# Fulmar_v_1_1_0.net
KiCad netlist of a schematic drawn in EAGLE
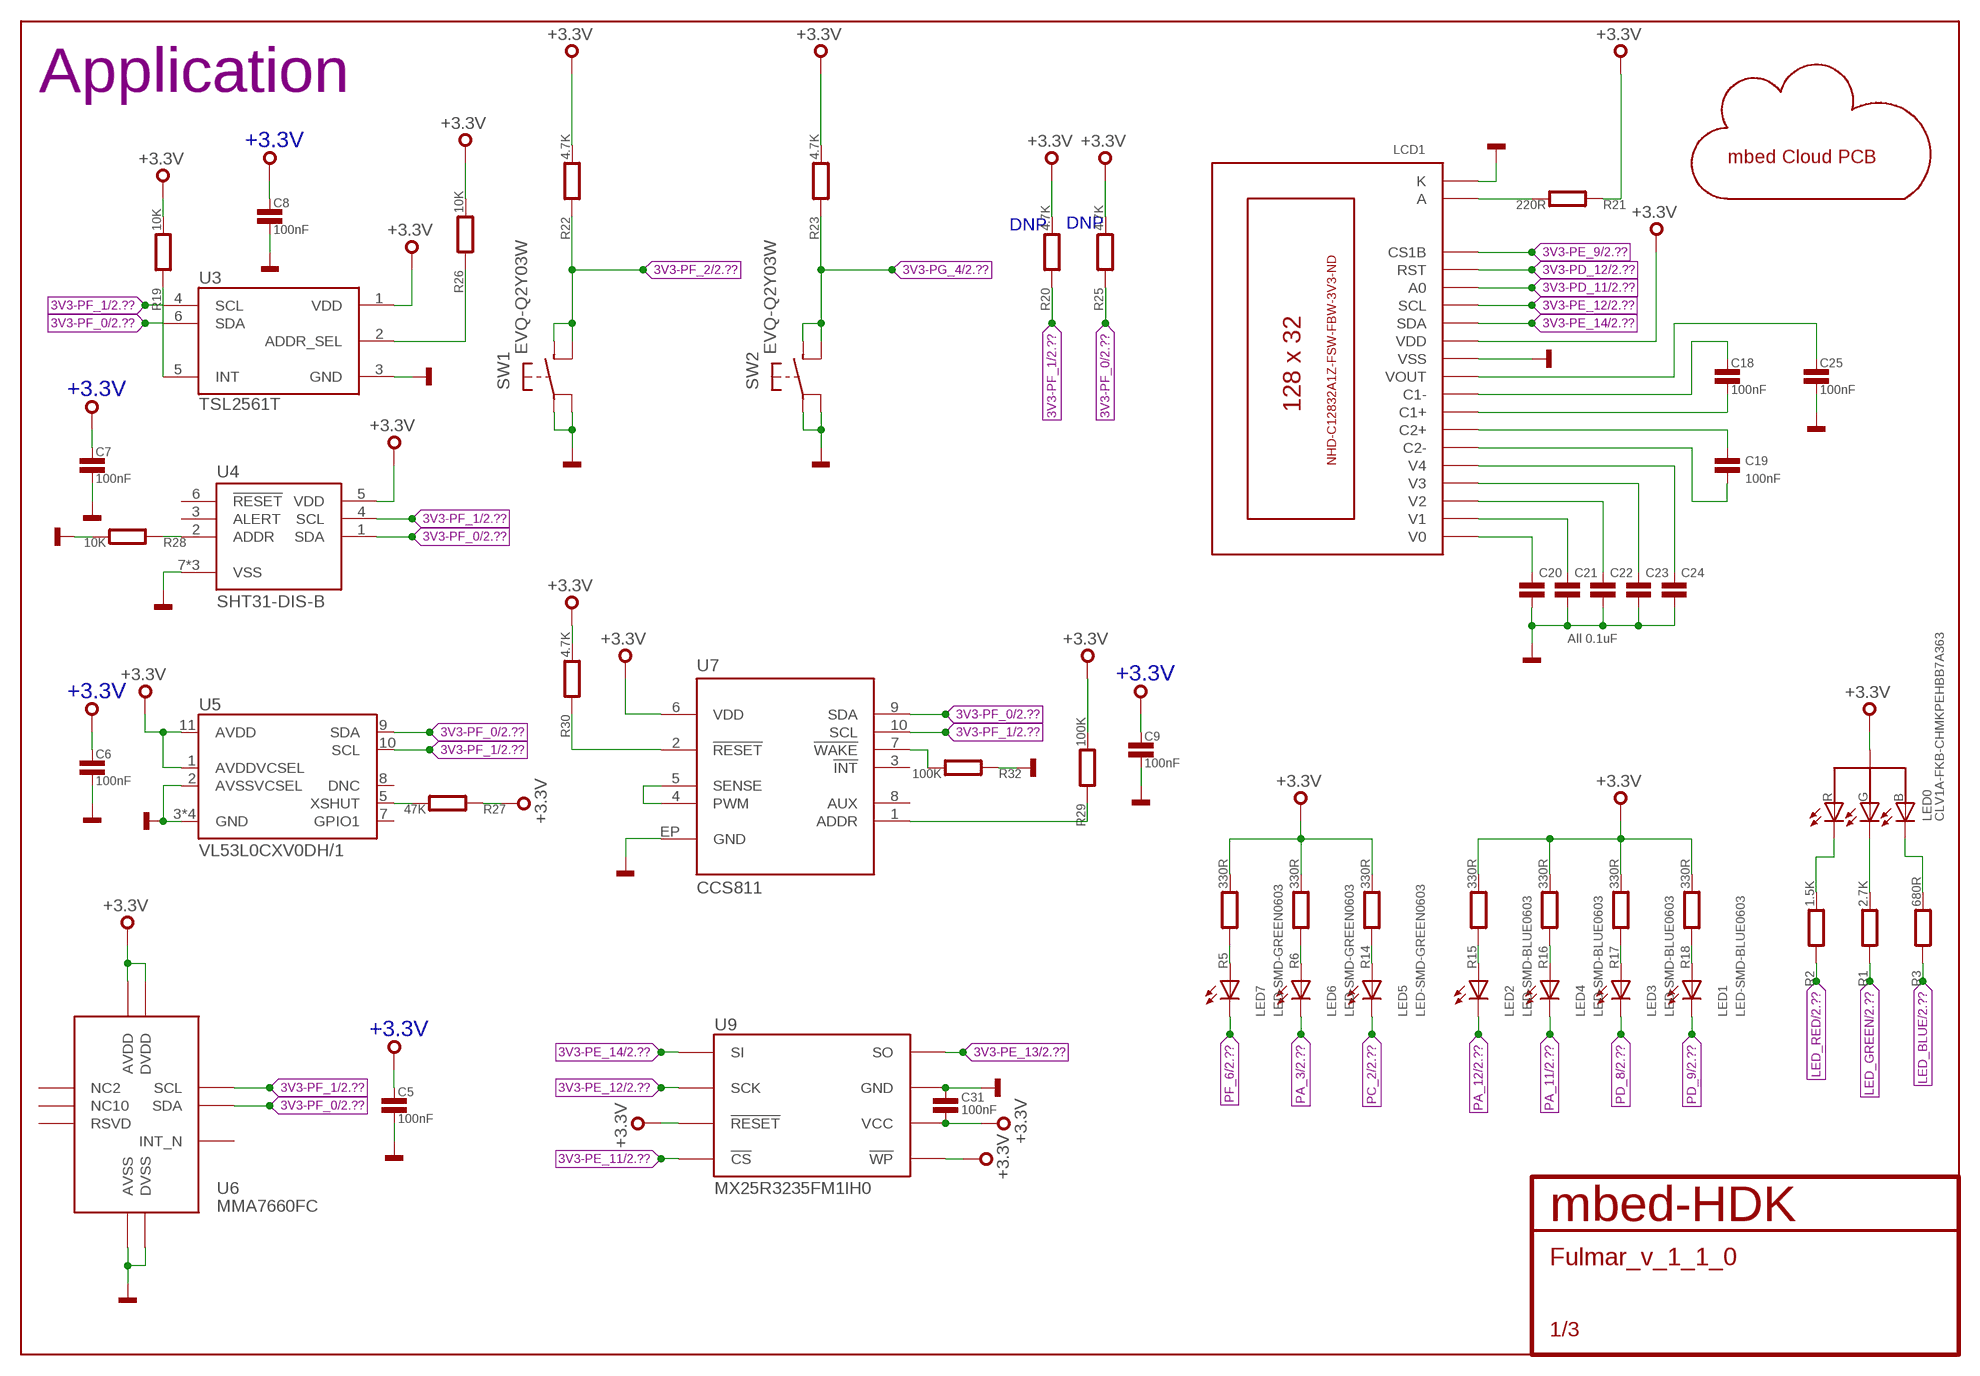
[diagram p0: schematic, sheet 1]
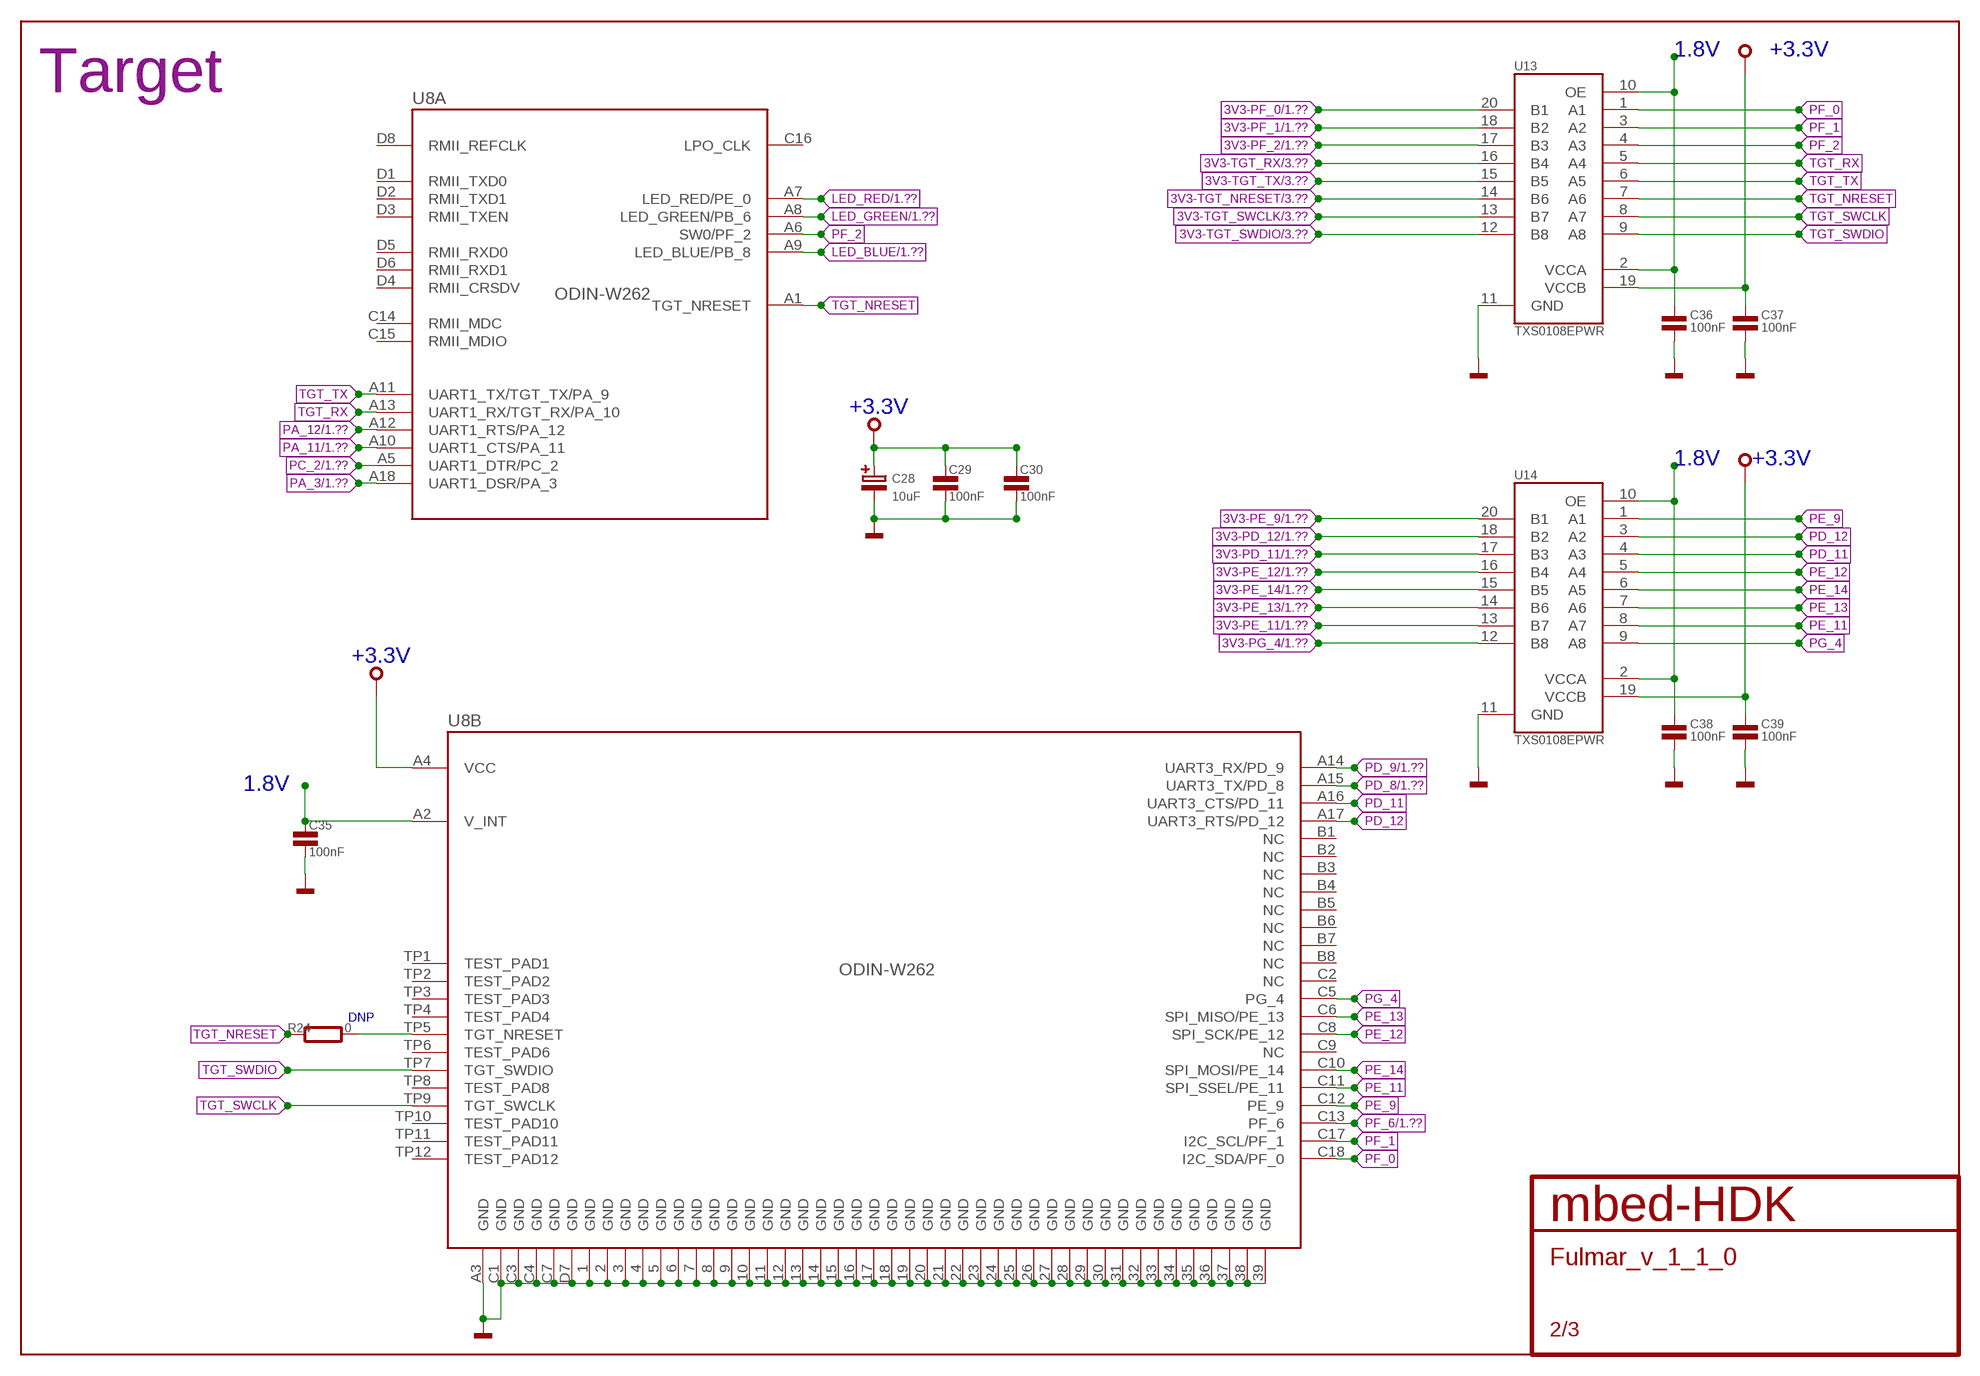
[diagram p1: schematic, sheet 2]
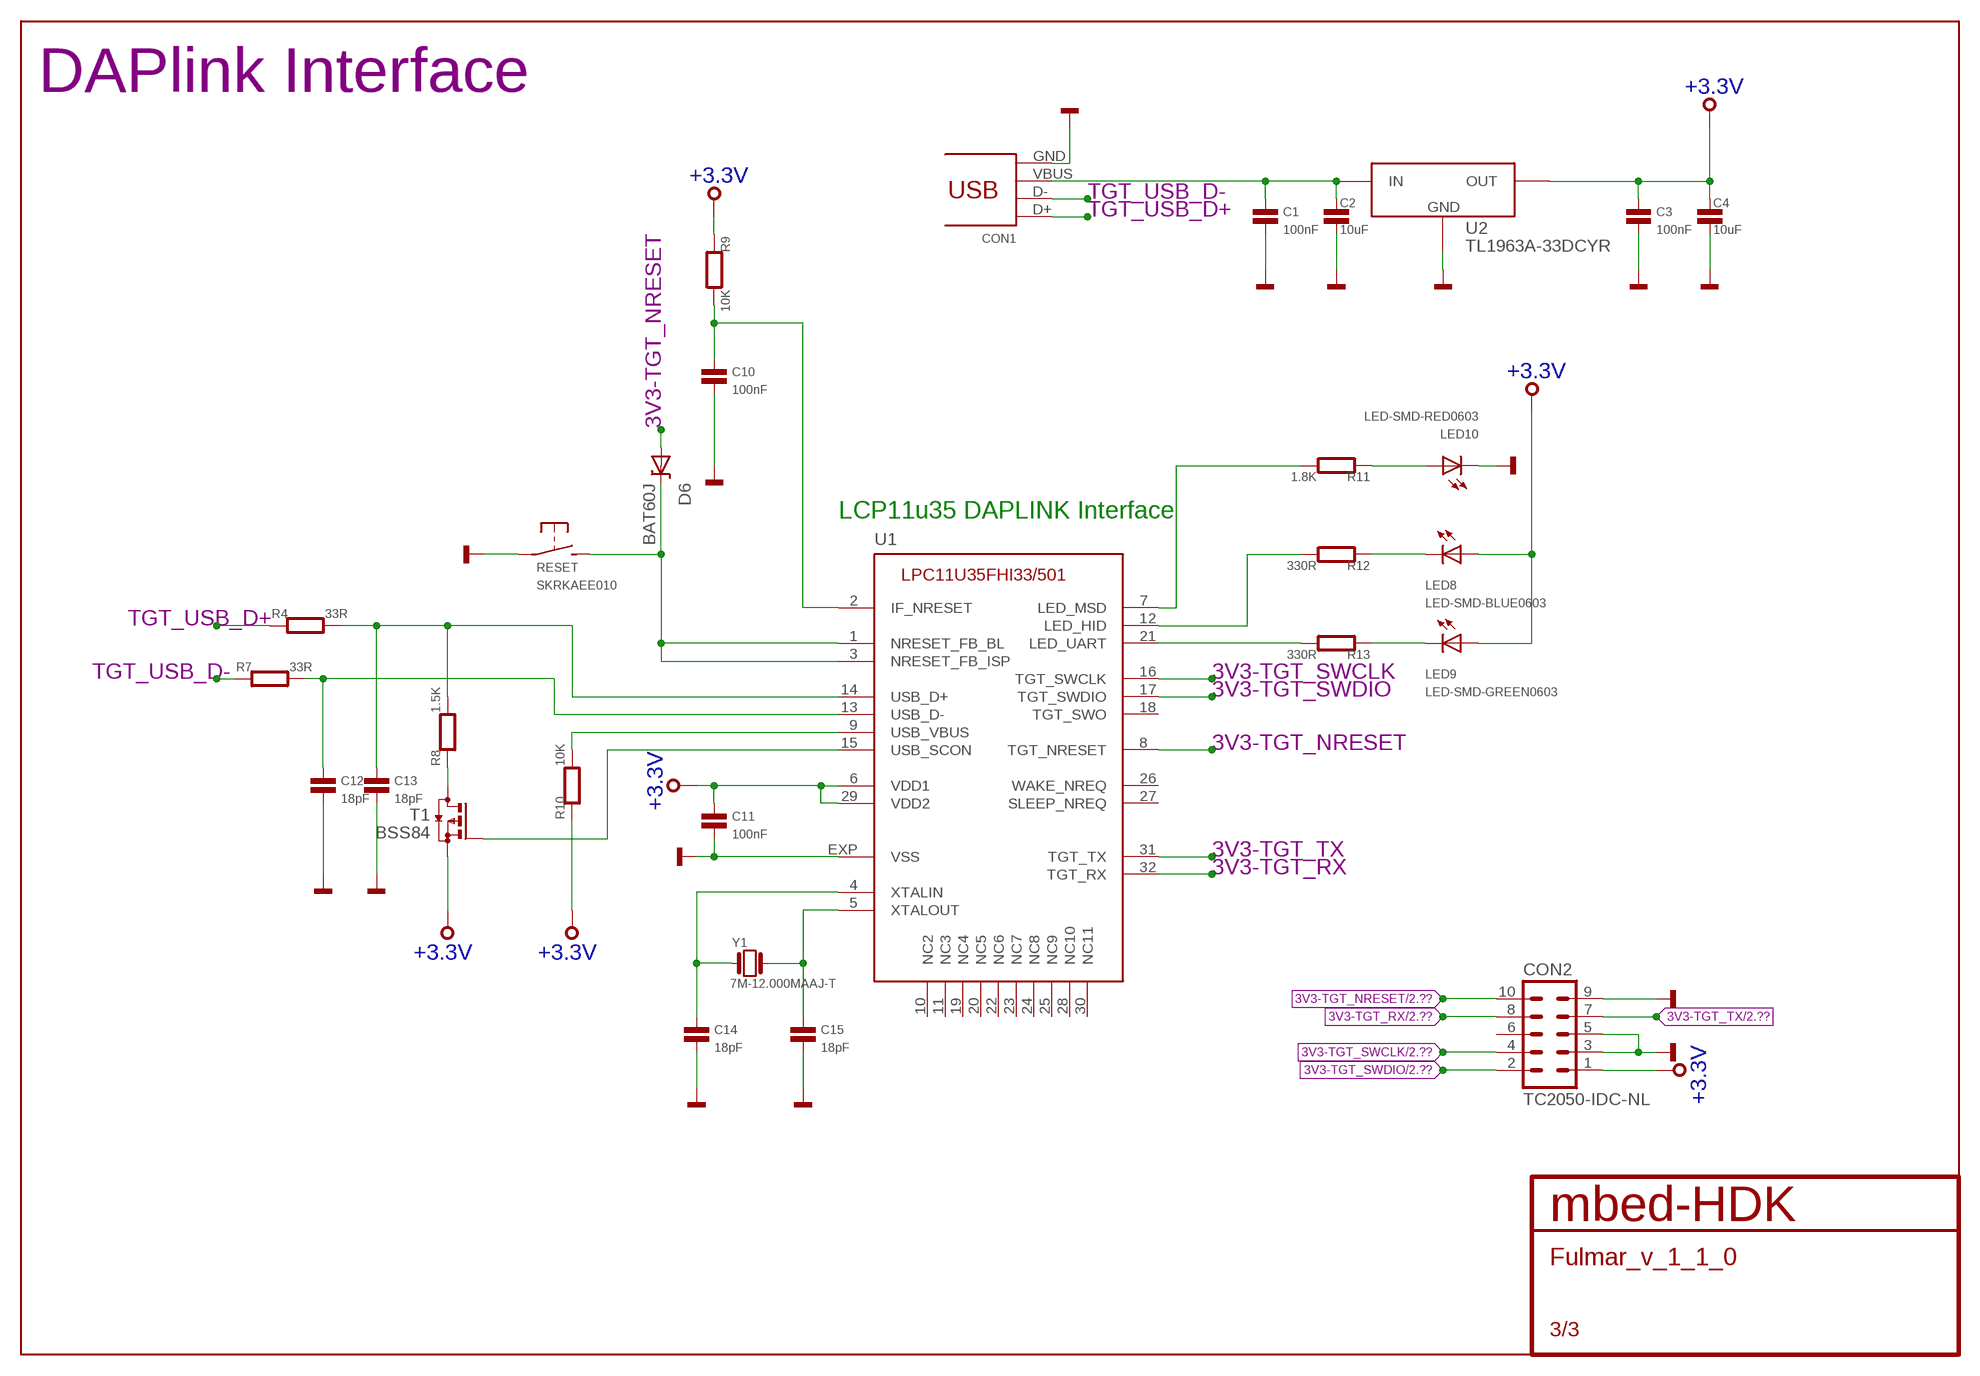
[diagram p2: schematic, sheet 3]

(export (version "E")
  (design (tool "Eeschema 10.0.6"))
  (components
    (comp (ref "C1")
      (value "100nF")
      (footprint "eagle-import:0402")
      (libsource (lib "eagle-import") (part "mbed-HDK-RLCQ_CAPACITOR0402"))
    )
    (comp (ref "C2")
      (value "10uF")
      (footprint "eagle-import:0603")
      (libsource (lib "eagle-import") (part "CAPACITOR0603"))
    )
    (comp (ref "C3")
      (value "100nF")
      (footprint "eagle-import:0402")
      (libsource (lib "eagle-import") (part "mbed-HDK-RLCQ_CAPACITOR0402"))
    )
    (comp (ref "C4")
      (value "10uF")
      (footprint "eagle-import:0603")
      (libsource (lib "eagle-import") (part "CAPACITOR0603"))
    )
    (comp (ref "C10")
      (value "100nF")
      (footprint "eagle-import:0402")
      (libsource (lib "eagle-import") (part "mbed-HDK-RLCQ_CAPACITOR0402"))
    )
    (comp (ref "C11")
      (value "100nF")
      (footprint "eagle-import:0402")
      (libsource (lib "eagle-import") (part "mbed-HDK-RLCQ_CAPACITOR0402"))
    )
    (comp (ref "C12")
      (value "18pF")
      (footprint "eagle-import:0402")
      (libsource (lib "eagle-import") (part "mbed-HDK-RLCQ_CAPACITOR0402"))
    )
    (comp (ref "C13")
      (value "18pF")
      (footprint "eagle-import:0402")
      (libsource (lib "eagle-import") (part "mbed-HDK-RLCQ_CAPACITOR0402"))
    )
    (comp (ref "C14")
      (value "18pF")
      (footprint "eagle-import:0402")
      (libsource (lib "eagle-import") (part "mbed-HDK-RLCQ_CAPACITOR0402"))
    )
    (comp (ref "C15")
      (value "18pF")
      (footprint "eagle-import:0402")
      (libsource (lib "eagle-import") (part "mbed-HDK-RLCQ_CAPACITOR0402"))
    )
    (comp (ref "CON1")
      (value "47346-0001")
      (footprint "eagle-import:USB-MICRO-B-H")
      (fields (field (name "MF") "MOLEX"))
      (libsource (lib "eagle-import") (part "47346-0001"))
    )
    (comp (ref "CON2")
      (value "TC2050-IDC-NL")
      (footprint "eagle-import:TC2050-IDC-NL")
      (libsource (lib "eagle-import") (part "TC2050-IDC-NL"))
    )
    (comp (ref "D6")
      (value "BAT60J")
      (footprint "eagle-import:SOD323")
      (fields (field (name "MF") "STMicroelectronics"))
      (libsource (lib "eagle-import") (part "BAT60J"))
    )
    (comp (ref "LED8")
      (value "LED-SMD-BLUE0603")
      (footprint "eagle-import:CHIPLED_0603")
      (fields (field (name "MF") "Wurth Electronics Inc"))
      (libsource (lib "eagle-import") (part "LED-SMD-BLUE0603"))
    )
    (comp (ref "LED9")
      (value "LED-SMD-GREEN0603")
      (footprint "eagle-import:CHIPLED_0603")
      (fields (field (name "MF") "Wurth Electronics Inc"))
      (libsource (lib "eagle-import") (part "LED-SMD-GREEN0603"))
    )
    (comp (ref "LED10")
      (value "LED-SMD-RED0603")
      (footprint "eagle-import:CHIPLED_0603")
      (fields (field (name "MF") "Wurth Electronics Inc"))
      (libsource (lib "eagle-import") (part "LED-SMD-RED0603"))
    )
    (comp (ref "R4")
      (value "33R")
      (footprint "eagle-import:0402")
      (libsource (lib "eagle-import") (part "mbed-HDK-RLCQ_RESISTOR0402"))
    )
    (comp (ref "R7")
      (value "33R")
      (footprint "eagle-import:0402")
      (libsource (lib "eagle-import") (part "mbed-HDK-RLCQ_RESISTOR0402"))
    )
    (comp (ref "R8")
      (value "1.5K")
      (footprint "eagle-import:0402")
      (libsource (lib "eagle-import") (part "mbed-HDK-RLCQ_RESISTOR0402"))
    )
    (comp (ref "R9")
      (value "10K")
      (footprint "eagle-import:0402")
      (libsource (lib "eagle-import") (part "mbed-HDK-RLCQ_RESISTOR0402"))
    )
    (comp (ref "R10")
      (value "10K")
      (footprint "eagle-import:0402")
      (libsource (lib "eagle-import") (part "mbed-HDK-RLCQ_RESISTOR0402"))
    )
    (comp (ref "R11")
      (value "1.8K")
      (footprint "eagle-import:0402")
      (libsource (lib "eagle-import") (part "mbed-HDK-RLCQ_RESISTOR0402"))
    )
    (comp (ref "R12")
      (value "330R")
      (footprint "eagle-import:0402")
      (libsource (lib "eagle-import") (part "mbed-HDK-RLCQ_RESISTOR0402"))
    )
    (comp (ref "R13")
      (value "330R")
      (footprint "eagle-import:0402")
      (libsource (lib "eagle-import") (part "mbed-HDK-RLCQ_RESISTOR0402"))
    )
    (comp (ref "RESET")
      (value "SKRKAEE010")
      (footprint "eagle-import:SKRKAEE010")
      (fields (field (name "MF") "ALPS"))
      (libsource (lib "eagle-import") (part "SKRKAEE010"))
    )
    (comp (ref "T1")
      (value "BSS84")
      (footprint "eagle-import:SOT23-3")
      (fields (field (name "MF") "Fairchild Semiconductor"))
      (libsource (lib "eagle-import") (part "BSS84"))
    )
    (comp (ref "U1")
      (value "IF_LPC11U35FHI33/501")
      (footprint "eagle-import:HVQFN33")
      (fields (field (name "MF") "NXP"))
      (libsource (lib "eagle-import") (part "IF_LPC11U35FHI33/501"))
    )
    (comp (ref "U2")
      (value "TL1963A-33DCYR")
      (footprint "eagle-import:SOT223")
      (fields (field (name "MF") "Texas Instruments"))
      (libsource (lib "eagle-import") (part "TL1963A-33DCYR"))
    )
    (comp (ref "Y1")
      (value "7M-12.000MAAJ-T")
      (footprint "eagle-import:3.2X.2.5")
      (fields (field (name "MF") "TXC"))
      (libsource (lib "eagle-import") (part "7M-12.000MAAJ-T"))
    )
    (comp (ref "C5")
      (value "100nF")
      (footprint "eagle-import:0603")
      (libsource (lib "eagle-import") (part "CAPACITOR0603"))
    )
    (comp (ref "C6")
      (value "100nF")
      (footprint "eagle-import:0603")
      (libsource (lib "eagle-import") (part "CAPACITOR0603"))
    )
    (comp (ref "C7")
      (value "100nF")
      (footprint "eagle-import:0603")
      (libsource (lib "eagle-import") (part "CAPACITOR0603"))
    )
    (comp (ref "C8")
      (value "100nF")
      (footprint "eagle-import:0603")
      (libsource (lib "eagle-import") (part "CAPACITOR0603"))
    )
    (comp (ref "C9")
      (value "100nF")
      (footprint "eagle-import:0603")
      (libsource (lib "eagle-import") (part "CAPACITOR0603"))
    )
    (comp (ref "C18")
      (value "100nF")
      (footprint "eagle-import:0402")
      (libsource (lib "eagle-import") (part "CAPACITOR0402"))
    )
    (comp (ref "C19")
      (value "100nF")
      (footprint "eagle-import:0402")
      (libsource (lib "eagle-import") (part "CAPACITOR0402"))
    )
    (comp (ref "C20")
      (value "100nF")
      (footprint "eagle-import:0402")
      (libsource (lib "eagle-import") (part "CAPACITOR0402"))
    )
    (comp (ref "C21")
      (value "100nF")
      (footprint "eagle-import:0402")
      (libsource (lib "eagle-import") (part "CAPACITOR0402"))
    )
    (comp (ref "C22")
      (value "100nF")
      (footprint "eagle-import:0402")
      (libsource (lib "eagle-import") (part "CAPACITOR0402"))
    )
    (comp (ref "C23")
      (value "100nF")
      (footprint "eagle-import:0402")
      (libsource (lib "eagle-import") (part "CAPACITOR0402"))
    )
    (comp (ref "C24")
      (value "100nF")
      (footprint "eagle-import:0402")
      (libsource (lib "eagle-import") (part "CAPACITOR0402"))
    )
    (comp (ref "C25")
      (value "100nF")
      (footprint "eagle-import:0402")
      (libsource (lib "eagle-import") (part "CAPACITOR0402"))
    )
    (comp (ref "C31")
      (value "100nF")
      (footprint "eagle-import:0603")
      (libsource (lib "eagle-import") (part "CAPACITOR0603"))
    )
    (comp (ref "LCD1")
      (value "C12832A1Z")
      (footprint "eagle-import:C12832A1Z")
      (libsource (lib "eagle-import") (part "C12832A1Z"))
    )
    (comp (ref "LED0")
      (value "CLV1A-FKB-CHMKPEHBB7A363")
      (footprint "eagle-import:CLV1A-FKB-CHMKPEHBB7A363")
      (fields (field (name "MF") "Cree"))
      (libsource (lib "eagle-import") (part "CLV1A-FKB-CHMKPEHBB7A363"))
    )
    (comp (ref "LED1")
      (value "LED-SMD-BLUE0603")
      (footprint "eagle-import:CHIPLED_0603")
      (fields (field (name "MF") "Wurth Electronics Inc"))
      (libsource (lib "eagle-import") (part "LED-SMD-BLUE0603"))
    )
    (comp (ref "LED2")
      (value "LED-SMD-BLUE0603")
      (footprint "eagle-import:CHIPLED_0603")
      (fields (field (name "MF") "Wurth Electronics Inc"))
      (libsource (lib "eagle-import") (part "LED-SMD-BLUE0603"))
    )
    (comp (ref "LED3")
      (value "LED-SMD-BLUE0603")
      (footprint "eagle-import:CHIPLED_0603")
      (fields (field (name "MF") "Wurth Electronics Inc"))
      (libsource (lib "eagle-import") (part "LED-SMD-BLUE0603"))
    )
    (comp (ref "LED4")
      (value "LED-SMD-BLUE0603")
      (footprint "eagle-import:CHIPLED_0603")
      (fields (field (name "MF") "Wurth Electronics Inc"))
      (libsource (lib "eagle-import") (part "LED-SMD-BLUE0603"))
    )
    (comp (ref "LED5")
      (value "LED-SMD-GREEN0603")
      (footprint "eagle-import:CHIPLED_0603")
      (fields (field (name "MF") "Wurth Electronics Inc"))
      (libsource (lib "eagle-import") (part "LED-SMD-GREEN0603"))
    )
    (comp (ref "LED6")
      (value "LED-SMD-GREEN0603")
      (footprint "eagle-import:CHIPLED_0603")
      (fields (field (name "MF") "Wurth Electronics Inc"))
      (libsource (lib "eagle-import") (part "LED-SMD-GREEN0603"))
    )
    (comp (ref "LED7")
      (value "LED-SMD-GREEN0603")
      (footprint "eagle-import:CHIPLED_0603")
      (fields (field (name "MF") "Wurth Electronics Inc"))
      (libsource (lib "eagle-import") (part "LED-SMD-GREEN0603"))
    )
    (comp (ref "R1")
      (value "2.7K")
      (footprint "eagle-import:0402")
      (libsource (lib "eagle-import") (part "RESISTOR0402"))
    )
    (comp (ref "R2")
      (value "1.5K")
      (footprint "eagle-import:0402")
      (libsource (lib "eagle-import") (part "RESISTOR0402"))
    )
    (comp (ref "R3")
      (value "680R")
      (footprint "eagle-import:0402")
      (libsource (lib "eagle-import") (part "RESISTOR0402"))
    )
    (comp (ref "R5")
      (value "330R")
      (footprint "eagle-import:0402")
      (libsource (lib "eagle-import") (part "RESISTOR0402"))
    )
    (comp (ref "R6")
      (value "330R")
      (footprint "eagle-import:0402")
      (libsource (lib "eagle-import") (part "RESISTOR0402"))
    )
    (comp (ref "R14")
      (value "330R")
      (footprint "eagle-import:0402")
      (libsource (lib "eagle-import") (part "RESISTOR0402"))
    )
    (comp (ref "R15")
      (value "330R")
      (footprint "eagle-import:0402")
      (libsource (lib "eagle-import") (part "RESISTOR0402"))
    )
    (comp (ref "R16")
      (value "330R")
      (footprint "eagle-import:0402")
      (libsource (lib "eagle-import") (part "RESISTOR0402"))
    )
    (comp (ref "R17")
      (value "330R")
      (footprint "eagle-import:0402")
      (libsource (lib "eagle-import") (part "RESISTOR0402"))
    )
    (comp (ref "R18")
      (value "330R")
      (footprint "eagle-import:0402")
      (libsource (lib "eagle-import") (part "RESISTOR0402"))
    )
    (comp (ref "R19")
      (value "10K")
      (footprint "eagle-import:0402")
      (libsource (lib "eagle-import") (part "RESISTOR0402"))
    )
    (comp (ref "R20")
      (value "4.7K")
      (footprint "eagle-import:0402")
      (libsource (lib "eagle-import") (part "RESISTOR0402"))
    )
    (comp (ref "R21")
      (value "220R")
      (footprint "eagle-import:0402")
      (libsource (lib "eagle-import") (part "RESISTOR0402"))
    )
    (comp (ref "R22")
      (value "4.7K")
      (footprint "eagle-import:0402")
      (libsource (lib "eagle-import") (part "RESISTOR0402"))
    )
    (comp (ref "R23")
      (value "4.7K")
      (footprint "eagle-import:0402")
      (libsource (lib "eagle-import") (part "RESISTOR0402"))
    )
    (comp (ref "R25")
      (value "4.7K")
      (footprint "eagle-import:0402")
      (libsource (lib "eagle-import") (part "RESISTOR0402"))
    )
    (comp (ref "R26")
      (value "10K")
      (footprint "eagle-import:0402")
      (libsource (lib "eagle-import") (part "RESISTOR0402"))
    )
    (comp (ref "R27")
      (value "47K")
      (footprint "eagle-import:0402")
      (libsource (lib "eagle-import") (part "RESISTOR0402"))
    )
    (comp (ref "R28")
      (value "10K")
      (footprint "eagle-import:0402")
      (libsource (lib "eagle-import") (part "RESISTOR0402"))
    )
    (comp (ref "R29")
      (value "100K")
      (footprint "eagle-import:0402")
      (libsource (lib "eagle-import") (part "RESISTOR0402"))
    )
    (comp (ref "R30")
      (value "4.7K")
      (footprint "eagle-import:0402")
      (libsource (lib "eagle-import") (part "RESISTOR0402"))
    )
    (comp (ref "R32")
      (value "100K")
      (footprint "eagle-import:0402")
      (libsource (lib "eagle-import") (part "RESISTOR0402"))
    )
    (comp (ref "SW1")
      (value "EVQ-Q2Y03W")
      (footprint "eagle-import:EVQ-Q2Y03W")
      (fields (field (name "MF") "Panasonic"))
      (libsource (lib "eagle-import") (part "EVQ-Q2Y03W"))
    )
    (comp (ref "SW2")
      (value "EVQ-Q2Y03W")
      (footprint "eagle-import:EVQ-Q2Y03W")
      (fields (field (name "MF") "Panasonic"))
      (libsource (lib "eagle-import") (part "EVQ-Q2Y03W"))
    )
    (comp (ref "U$2")
      (value "MBEDCLOUDPCB")
      (footprint "eagle-import:MBEDCLOUDPCB")
      (libsource (lib "eagle-import") (part "MBEDCLOUDPCB"))
    )
    (comp (ref "U3")
      (value "TSL2561T")
      (footprint "eagle-import:6-TMB")
      (fields (field (name "MF") "ams"))
      (libsource (lib "eagle-import") (part "TSL2561T"))
    )
    (comp (ref "U4")
      (value "SHT31-DIS-B")
      (footprint "eagle-import:8-DFN")
      (fields (field (name "MF") "Sensirion"))
      (libsource (lib "eagle-import") (part "SHT31-DIS-B"))
    )
    (comp (ref "U5")
      (value "VL53L0CXV0DH/1")
      (footprint "eagle-import:VL53L0CXV0DH_1")
      (fields (field (name "MF") "ST Microelectronics"))
      (libsource (lib "eagle-import") (part "VL53L0CXV0DH/1"))
    )
    (comp (ref "U6")
      (value "MMA7660FC")
      (footprint "eagle-import:DFN10-3X3MM")
      (fields (field (name "MF") "NXP"))
      (libsource (lib "eagle-import") (part "MMA7660FC"))
    )
    (comp (ref "U7")
      (value "CCS811")
      (footprint "eagle-import:LGA10")
      (fields (field (name "MF") "ams"))
      (libsource (lib "eagle-import") (part "CCS811"))
    )
    (comp (ref "U9")
      (value "MX25R3235FM1IH0")
      (footprint "eagle-import:SO8")
      (fields (field (name "MF") "Macronix"))
      (libsource (lib "eagle-import") (part "MX25R3235FM1IH0"))
    )
    (comp (ref "C28")
      (value "10uF")
      (footprint "eagle-import:SMC_B")
      (fields (field (name "MF") "Kemet"))
      (libsource (lib "eagle-import") (part "CAPACITOR-POLARISEDB"))
    )
    (comp (ref "C29")
      (value "100nF")
      (footprint "eagle-import:0603")
      (libsource (lib "eagle-import") (part "CAPACITOR0603"))
    )
    (comp (ref "C30")
      (value "100nF")
      (footprint "eagle-import:0603")
      (libsource (lib "eagle-import") (part "CAPACITOR0603"))
    )
    (comp (ref "C35")
      (value "100nF")
      (footprint "eagle-import:0603")
      (libsource (lib "eagle-import") (part "CAPACITOR0603"))
    )
    (comp (ref "C36")
      (value "100nF")
      (footprint "eagle-import:0603")
      (libsource (lib "eagle-import") (part "CAPACITOR0603"))
    )
    (comp (ref "C37")
      (value "100nF")
      (footprint "eagle-import:0603")
      (libsource (lib "eagle-import") (part "CAPACITOR0603"))
    )
    (comp (ref "C38")
      (value "100nF")
      (footprint "eagle-import:0603")
      (libsource (lib "eagle-import") (part "CAPACITOR0603"))
    )
    (comp (ref "C39")
      (value "100nF")
      (footprint "eagle-import:0603")
      (libsource (lib "eagle-import") (part "CAPACITOR0603"))
    )
    (comp (ref "R24")
      (value "0")
      (footprint "eagle-import:0402")
      (libsource (lib "eagle-import") (part "RESISTOR0402"))
    )
    (comp (ref "U8")
      (value "ODIN-W262")
      (footprint "eagle-import:ODIN-88")
      (libsource (lib "eagle-import") (part "ODIN-W262"))
    )
    (comp (ref "U13")
      (value "TXS0108EPWR")
      (footprint "eagle-import:TSSOP-20")
      (fields (field (name "MF") "Texas Instruments"))
      (libsource (lib "eagle-import") (part "TXS0108EPWR"))
    )
    (comp (ref "U14")
      (value "TXS0108EPWR")
      (footprint "eagle-import:TSSOP-20")
      (fields (field (name "MF") "Texas Instruments"))
      (libsource (lib "eagle-import") (part "TXS0108EPWR"))
    )
  )
  (nets
    (net (code "1") (name "+3.3V") (class "Default")
      (node (ref "C11") (pin "1") (pinfunction "P$1_1") (pintype "passive"))
      (node (ref "C28") (pin "+") (pinfunction "+_+") (pintype "passive"))
      (node (ref "C29") (pin "1") (pinfunction "P$1_1") (pintype "passive"))
      (node (ref "C3") (pin "1") (pinfunction "P$1_1") (pintype "passive"))
      (node (ref "C30") (pin "1") (pinfunction "P$1_1") (pintype "passive"))
      (node (ref "C31") (pin "2") (pinfunction "P$2_2") (pintype "passive"))
      (node (ref "C37") (pin "1") (pinfunction "P$1_1") (pintype "passive"))
      (node (ref "C39") (pin "1") (pinfunction "P$1_1") (pintype "passive"))
      (node (ref "C4") (pin "1") (pinfunction "P$1_1") (pintype "passive"))
      (node (ref "C5") (pin "1") (pinfunction "P$1_1") (pintype "passive"))
      (node (ref "C6") (pin "1") (pinfunction "P$1_1") (pintype "passive"))
      (node (ref "C7") (pin "1") (pinfunction "P$1_1") (pintype "passive"))
      (node (ref "C8") (pin "1") (pinfunction "P$1_1") (pintype "passive"))
      (node (ref "C9") (pin "1") (pinfunction "P$1_1") (pintype "passive"))
      (node (ref "CON2") (pin "1") (pinfunction "1_1") (pintype "passive"))
      (node (ref "LCD1") (pin "P$12") (pinfunction "VDD_P$12") (pintype "bidirectional"))
      (node (ref "LED0") (pin "2") (pinfunction "2_2") (pintype "passive"))
      (node (ref "LED8") (pin "A") (pinfunction "A_A") (pintype "passive"))
      (node (ref "LED9") (pin "A") (pinfunction "A_A") (pintype "passive"))
      (node (ref "R10") (pin "1") (pinfunction "P$1_1") (pintype "passive"))
      (node (ref "R14") (pin "2") (pinfunction "P$2_2") (pintype "passive"))
      (node (ref "R15") (pin "2") (pinfunction "P$2_2") (pintype "passive"))
      (node (ref "R16") (pin "2") (pinfunction "P$2_2") (pintype "passive"))
      (node (ref "R17") (pin "2") (pinfunction "P$2_2") (pintype "passive"))
      (node (ref "R18") (pin "2") (pinfunction "P$2_2") (pintype "passive"))
      (node (ref "R19") (pin "2") (pinfunction "P$2_2") (pintype "passive"))
      (node (ref "R20") (pin "2") (pinfunction "P$2_2") (pintype "passive"))
      (node (ref "R21") (pin "1") (pinfunction "P$1_1") (pintype "passive"))
      (node (ref "R22") (pin "2") (pinfunction "P$2_2") (pintype "passive"))
      (node (ref "R23") (pin "2") (pinfunction "P$2_2") (pintype "passive"))
      (node (ref "R25") (pin "2") (pinfunction "P$2_2") (pintype "passive"))
      (node (ref "R26") (pin "2") (pinfunction "P$2_2") (pintype "passive"))
      (node (ref "R27") (pin "1") (pinfunction "P$1_1") (pintype "passive"))
      (node (ref "R29") (pin "2") (pinfunction "P$2_2") (pintype "passive"))
      (node (ref "R30") (pin "2") (pinfunction "P$2_2") (pintype "passive"))
      (node (ref "R5") (pin "2") (pinfunction "P$2_2") (pintype "passive"))
      (node (ref "R6") (pin "2") (pinfunction "P$2_2") (pintype "passive"))
      (node (ref "R9") (pin "1") (pinfunction "P$1_1") (pintype "passive"))
      (node (ref "T1") (pin "2") (pinfunction "S_2") (pintype "passive"))
      (node (ref "U1") (pin "29") (pinfunction "VDD2_29") (pintype "bidirectional"))
      (node (ref "U1") (pin "6") (pinfunction "VDD1_6") (pintype "bidirectional"))
      (node (ref "U13") (pin "19") (pinfunction "VCCB_19") (pintype "bidirectional"))
      (node (ref "U14") (pin "19") (pinfunction "VCCB_19") (pintype "bidirectional"))
      (node (ref "U2") (pin "3") (pinfunction "OUT_3") (pintype "bidirectional"))
      (node (ref "U3") (pin "1") (pinfunction "VDD_1") (pintype "bidirectional"))
      (node (ref "U4") (pin "5") (pinfunction "VDD_5") (pintype "bidirectional"))
      (node (ref "U5") (pin "1") (pinfunction "AVDDVCSEL_1") (pintype "bidirectional"))
      (node (ref "U5") (pin "11") (pinfunction "AVDD_11") (pintype "bidirectional"))
      (node (ref "U6") (pin "P$3") (pinfunction "AVDD_P$3") (pintype "bidirectional"))
      (node (ref "U6") (pin "P$9") (pinfunction "DVDD_P$9") (pintype "bidirectional"))
      (node (ref "U7") (pin "6") (pinfunction "VDD_6") (pintype "bidirectional"))
      (node (ref "U8") (pin "A4") (pinfunction "VCC_A4") (pintype "power_in"))
      (node (ref "U9") (pin "3") (pinfunction "~{WP}_3") (pintype "bidirectional"))
      (node (ref "U9") (pin "7") (pinfunction "~{RESET}_7") (pintype "bidirectional"))
      (node (ref "U9") (pin "8") (pinfunction "VCC_8") (pintype "bidirectional"))
    )
    (net (code "2") (name "1.8V") (class "Default")
      (node (ref "C35") (pin "1") (pinfunction "P$1_1") (pintype "passive"))
      (node (ref "C36") (pin "1") (pinfunction "P$1_1") (pintype "passive"))
      (node (ref "C38") (pin "1") (pinfunction "P$1_1") (pintype "passive"))
      (node (ref "U13") (pin "10") (pinfunction "OE_10") (pintype "bidirectional"))
      (node (ref "U13") (pin "2") (pinfunction "VCCA_2") (pintype "bidirectional"))
      (node (ref "U14") (pin "10") (pinfunction "OE_10") (pintype "bidirectional"))
      (node (ref "U14") (pin "2") (pinfunction "VCCA_2") (pintype "bidirectional"))
      (node (ref "U8") (pin "A2") (pinfunction "V_INT_A2") (pintype "power_in"))
    )
    (net (code "3") (name "3V3-PD_11") (class "Default")
      (node (ref "LCD1") (pin "P$15") (pinfunction "A0_P$15") (pintype "bidirectional"))
      (node (ref "U14") (pin "17") (pinfunction "B3_17") (pintype "bidirectional"))
    )
    (net (code "4") (name "3V3-PD_12") (class "Default")
      (node (ref "LCD1") (pin "P$16") (pinfunction "RST_P$16") (pintype "bidirectional"))
      (node (ref "U14") (pin "18") (pinfunction "B2_18") (pintype "bidirectional"))
    )
    (net (code "5") (name "3V3-PE_9") (class "Default")
      (node (ref "LCD1") (pin "P$17") (pinfunction "CS1B_P$17") (pintype "bidirectional"))
      (node (ref "U14") (pin "20") (pinfunction "B1_20") (pintype "bidirectional"))
    )
    (net (code "6") (name "3V3-PE_11") (class "Default")
      (node (ref "U14") (pin "13") (pinfunction "B7_13") (pintype "bidirectional"))
      (node (ref "U9") (pin "1") (pinfunction "~{CS}_1") (pintype "bidirectional"))
    )
    (net (code "7") (name "3V3-PE_12") (class "Default")
      (node (ref "LCD1") (pin "P$14") (pinfunction "SCL_P$14") (pintype "bidirectional"))
      (node (ref "U14") (pin "16") (pinfunction "B4_16") (pintype "bidirectional"))
      (node (ref "U9") (pin "6") (pinfunction "SCK_6") (pintype "bidirectional"))
    )
    (net (code "8") (name "3V3-PE_13") (class "Default")
      (node (ref "U14") (pin "14") (pinfunction "B6_14") (pintype "bidirectional"))
      (node (ref "U9") (pin "2") (pinfunction "SO_2") (pintype "bidirectional"))
    )
    (net (code "9") (name "3V3-PE_14") (class "Default")
      (node (ref "LCD1") (pin "P$13") (pinfunction "SDA_P$13") (pintype "bidirectional"))
      (node (ref "U14") (pin "15") (pinfunction "B5_15") (pintype "bidirectional"))
      (node (ref "U9") (pin "5") (pinfunction "SI_5") (pintype "bidirectional"))
    )
    (net (code "10") (name "3V3-PF_0") (class "Default")
      (node (ref "R25") (pin "1") (pinfunction "P$1_1") (pintype "passive"))
      (node (ref "U13") (pin "20") (pinfunction "B1_20") (pintype "bidirectional"))
      (node (ref "U3") (pin "6") (pinfunction "SDA_6") (pintype "bidirectional"))
      (node (ref "U4") (pin "1") (pinfunction "SDA_1") (pintype "bidirectional"))
      (node (ref "U5") (pin "9") (pinfunction "SDA_9") (pintype "bidirectional"))
      (node (ref "U6") (pin "P$7") (pinfunction "SDA_P$7") (pintype "bidirectional"))
      (node (ref "U7") (pin "9") (pinfunction "SDA_9") (pintype "bidirectional"))
    )
    (net (code "11") (name "3V3-PF_1") (class "Default")
      (node (ref "R20") (pin "1") (pinfunction "P$1_1") (pintype "passive"))
      (node (ref "U13") (pin "18") (pinfunction "B2_18") (pintype "bidirectional"))
      (node (ref "U3") (pin "4") (pinfunction "SCL_4") (pintype "bidirectional"))
      (node (ref "U4") (pin "4") (pinfunction "SCL_4") (pintype "bidirectional"))
      (node (ref "U5") (pin "10") (pinfunction "SCL_10") (pintype "bidirectional"))
      (node (ref "U6") (pin "P$6") (pinfunction "SCL_P$6") (pintype "bidirectional"))
      (node (ref "U7") (pin "10") (pinfunction "SCL_10") (pintype "bidirectional"))
    )
    (net (code "12") (name "3V3-PF_2") (class "Default")
      (node (ref "R22") (pin "1") (pinfunction "P$1_1") (pintype "passive"))
      (node (ref "SW1") (pin "P$3") (pinfunction "B1_P$3") (pintype "passive"))
      (node (ref "SW1") (pin "P$4") (pinfunction "B2_P$4") (pintype "passive"))
      (node (ref "U13") (pin "17") (pinfunction "B3_17") (pintype "bidirectional"))
    )
    (net (code "13") (name "3V3-PG_4") (class "Default")
      (node (ref "R23") (pin "1") (pinfunction "P$1_1") (pintype "passive"))
      (node (ref "SW2") (pin "P$3") (pinfunction "B1_P$3") (pintype "passive"))
      (node (ref "SW2") (pin "P$4") (pinfunction "B2_P$4") (pintype "passive"))
      (node (ref "U14") (pin "12") (pinfunction "B8_12") (pintype "bidirectional"))
    )
    (net (code "14") (name "3V3-TGT_NRESET") (class "Default")
      (node (ref "CON2") (pin "10") (pinfunction "10_10") (pintype "passive"))
      (node (ref "D6") (pin "A") (pinfunction "A_A") (pintype "passive"))
      (node (ref "U1") (pin "8") (pinfunction "TGT_NRESET_8") (pintype "bidirectional"))
      (node (ref "U13") (pin "14") (pinfunction "B6_14") (pintype "bidirectional"))
    )
    (net (code "15") (name "3V3-TGT_RX") (class "Default")
      (node (ref "CON2") (pin "8") (pinfunction "8_8") (pintype "passive"))
      (node (ref "U1") (pin "32") (pinfunction "TGT_RX_32") (pintype "bidirectional"))
      (node (ref "U13") (pin "16") (pinfunction "B4_16") (pintype "bidirectional"))
    )
    (net (code "16") (name "3V3-TGT_SWCLK") (class "Default")
      (node (ref "CON2") (pin "4") (pinfunction "4_4") (pintype "passive"))
      (node (ref "U1") (pin "16") (pinfunction "TGT_SWCLK_16") (pintype "bidirectional"))
      (node (ref "U13") (pin "13") (pinfunction "B7_13") (pintype "bidirectional"))
    )
    (net (code "17") (name "3V3-TGT_SWDIO") (class "Default")
      (node (ref "CON2") (pin "2") (pinfunction "2_2") (pintype "passive"))
      (node (ref "U1") (pin "17") (pinfunction "TGT_SWDIO_17") (pintype "bidirectional"))
      (node (ref "U13") (pin "12") (pinfunction "B8_12") (pintype "bidirectional"))
    )
    (net (code "18") (name "3V3-TGT_TX") (class "Default")
      (node (ref "CON2") (pin "7") (pinfunction "7_7") (pintype "passive"))
      (node (ref "U1") (pin "31") (pinfunction "TGT_TX_31") (pintype "bidirectional"))
      (node (ref "U13") (pin "15") (pinfunction "B5_15") (pintype "bidirectional"))
    )
    (net (code "19") (name "GND") (class "Default")
      (node (ref "C1") (pin "2") (pinfunction "P$2_2") (pintype "passive"))
      (node (ref "C10") (pin "2") (pinfunction "P$2_2") (pintype "passive"))
      (node (ref "C11") (pin "2") (pinfunction "P$2_2") (pintype "passive"))
      (node (ref "C12") (pin "2") (pinfunction "P$2_2") (pintype "passive"))
      (node (ref "C13") (pin "2") (pinfunction "P$2_2") (pintype "passive"))
      (node (ref "C14") (pin "2") (pinfunction "P$2_2") (pintype "passive"))
      (node (ref "C15") (pin "2") (pinfunction "P$2_2") (pintype "passive"))
      (node (ref "C2") (pin "2") (pinfunction "P$2_2") (pintype "passive"))
      (node (ref "C20") (pin "2") (pinfunction "P$2_2") (pintype "passive"))
      (node (ref "C21") (pin "2") (pinfunction "P$2_2") (pintype "passive"))
      (node (ref "C22") (pin "2") (pinfunction "P$2_2") (pintype "passive"))
      (node (ref "C23") (pin "2") (pinfunction "P$2_2") (pintype "passive"))
      (node (ref "C24") (pin "2") (pinfunction "P$2_2") (pintype "passive"))
      (node (ref "C25") (pin "2") (pinfunction "P$2_2") (pintype "passive"))
      (node (ref "C28") (pin "-") (pinfunction "-_-") (pintype "passive"))
      (node (ref "C29") (pin "2") (pinfunction "P$2_2") (pintype "passive"))
      (node (ref "C3") (pin "2") (pinfunction "P$2_2") (pintype "passive"))
      (node (ref "C30") (pin "2") (pinfunction "P$2_2") (pintype "passive"))
      (node (ref "C31") (pin "1") (pinfunction "P$1_1") (pintype "passive"))
      (node (ref "C35") (pin "2") (pinfunction "P$2_2") (pintype "passive"))
      (node (ref "C36") (pin "2") (pinfunction "P$2_2") (pintype "passive"))
      (node (ref "C37") (pin "2") (pinfunction "P$2_2") (pintype "passive"))
      (node (ref "C38") (pin "2") (pinfunction "P$2_2") (pintype "passive"))
      (node (ref "C39") (pin "2") (pinfunction "P$2_2") (pintype "passive"))
      (node (ref "C4") (pin "2") (pinfunction "P$2_2") (pintype "passive"))
      (node (ref "C5") (pin "2") (pinfunction "P$2_2") (pintype "passive"))
      (node (ref "C6") (pin "2") (pinfunction "P$2_2") (pintype "passive"))
      (node (ref "C7") (pin "2") (pinfunction "P$2_2") (pintype "passive"))
      (node (ref "C8") (pin "2") (pinfunction "P$2_2") (pintype "passive"))
      (node (ref "C9") (pin "2") (pinfunction "P$2_2") (pintype "passive"))
      (node (ref "CON1") (pin "GND") (pinfunction "GND_GND") (pintype "bidirectional"))
      (node (ref "CON2") (pin "3") (pinfunction "3_3") (pintype "passive"))
      (node (ref "CON2") (pin "5") (pinfunction "5_5") (pintype "passive"))
      (node (ref "CON2") (pin "9") (pinfunction "9_9") (pintype "passive"))
      (node (ref "LCD1") (pin "K") (pinfunction "K_K") (pintype "bidirectional"))
      (node (ref "LCD1") (pin "P$11") (pinfunction "VSS_P$11") (pintype "bidirectional"))
      (node (ref "LED10") (pin "C") (pinfunction "C_C") (pintype "passive"))
      (node (ref "R28") (pin "2") (pinfunction "P$2_2") (pintype "passive"))
      (node (ref "R32") (pin "1") (pinfunction "P$1_1") (pintype "passive"))
      (node (ref "RESET") (pin "P$1") (pinfunction "P_P$1") (pintype "passive"))
      (node (ref "SW1") (pin "P$1") (pinfunction "A1_P$1") (pintype "passive"))
      (node (ref "SW1") (pin "P$2") (pinfunction "A2_P$2") (pintype "passive"))
      (node (ref "SW2") (pin "P$1") (pinfunction "A1_P$1") (pintype "passive"))
      (node (ref "SW2") (pin "P$2") (pinfunction "A2_P$2") (pintype "passive"))
      (node (ref "U1") (pin "EXP") (pinfunction "VSS_EXP") (pintype "bidirectional"))
      (node (ref "U13") (pin "11") (pinfunction "GND_11") (pintype "bidirectional"))
      (node (ref "U14") (pin "11") (pinfunction "GND_11") (pintype "bidirectional"))
      (node (ref "U2") (pin "2") (pinfunction "GND_2") (pintype "bidirectional"))
      (node (ref "U2") (pin "4") (pinfunction "GND_4") (pintype "bidirectional"))
      (node (ref "U3") (pin "3") (pinfunction "GND_3") (pintype "bidirectional"))
      (node (ref "U4") (pin "7") (pinfunction "VSS_7") (pintype "bidirectional"))
      (node (ref "U4") (pin "8") (pinfunction "VSS_8") (pintype "bidirectional"))
      (node (ref "U4") (pin "9") (pinfunction "VSS_9") (pintype "bidirectional"))
      (node (ref "U5") (pin "12") (pinfunction "GND_12") (pintype "bidirectional"))
      (node (ref "U5") (pin "2") (pinfunction "AVSSVCSEL_2") (pintype "bidirectional"))
      (node (ref "U5") (pin "3") (pinfunction "GND_3") (pintype "bidirectional"))
      (node (ref "U5") (pin "4") (pinfunction "GND_4") (pintype "bidirectional"))
      (node (ref "U5") (pin "6") (pinfunction "GND_6") (pintype "bidirectional"))
      (node (ref "U6") (pin "P$4") (pinfunction "AVSS_P$4") (pintype "bidirectional"))
      (node (ref "U6") (pin "P$8") (pinfunction "DVSS_P$8") (pintype "bidirectional"))
      (node (ref "U7") (pin "EP") (pinfunction "GND_EP") (pintype "bidirectional"))
      (node (ref "U8") (pin "1") (pinfunction "GND_1") (pintype "power_in"))
      (node (ref "U8") (pin "10") (pinfunction "GND_10") (pintype "power_in"))
      (node (ref "U8") (pin "11") (pinfunction "GND_11") (pintype "power_in"))
      (node (ref "U8") (pin "12") (pinfunction "GND_12") (pintype "power_in"))
      (node (ref "U8") (pin "13") (pinfunction "GND_13") (pintype "power_in"))
      (node (ref "U8") (pin "14") (pinfunction "GND_14") (pintype "power_in"))
      (node (ref "U8") (pin "15") (pinfunction "GND_15") (pintype "power_in"))
      (node (ref "U8") (pin "16") (pinfunction "GND_16") (pintype "power_in"))
      (node (ref "U8") (pin "17") (pinfunction "GND_17") (pintype "power_in"))
      (node (ref "U8") (pin "18") (pinfunction "GND_18") (pintype "power_in"))
      (node (ref "U8") (pin "19") (pinfunction "GND_19") (pintype "power_in"))
      (node (ref "U8") (pin "2") (pinfunction "GND_2") (pintype "power_in"))
      (node (ref "U8") (pin "20") (pinfunction "GND_20") (pintype "power_in"))
      (node (ref "U8") (pin "21") (pinfunction "GND_21") (pintype "power_in"))
      (node (ref "U8") (pin "22") (pinfunction "GND_22") (pintype "power_in"))
      (node (ref "U8") (pin "23") (pinfunction "GND_23") (pintype "power_in"))
      (node (ref "U8") (pin "24") (pinfunction "GND_24") (pintype "power_in"))
      (node (ref "U8") (pin "25") (pinfunction "GND_25") (pintype "power_in"))
      (node (ref "U8") (pin "26") (pinfunction "GND_26") (pintype "power_in"))
      (node (ref "U8") (pin "27") (pinfunction "GND_27") (pintype "power_in"))
      (node (ref "U8") (pin "28") (pinfunction "GND_28") (pintype "power_in"))
      (node (ref "U8") (pin "29") (pinfunction "GND_29") (pintype "power_in"))
      (node (ref "U8") (pin "3") (pinfunction "GND_3") (pintype "power_in"))
      (node (ref "U8") (pin "30") (pinfunction "GND_30") (pintype "power_in"))
      (node (ref "U8") (pin "31") (pinfunction "GND_31") (pintype "power_in"))
      (node (ref "U8") (pin "32") (pinfunction "GND_32") (pintype "power_in"))
      (node (ref "U8") (pin "33") (pinfunction "GND_33") (pintype "power_in"))
      (node (ref "U8") (pin "34") (pinfunction "GND_34") (pintype "power_in"))
      (node (ref "U8") (pin "35") (pinfunction "GND_35") (pintype "power_in"))
      (node (ref "U8") (pin "36") (pinfunction "GND_36") (pintype "power_in"))
      (node (ref "U8") (pin "37") (pinfunction "GND_37") (pintype "power_in"))
      (node (ref "U8") (pin "38") (pinfunction "GND_38") (pintype "power_in"))
      (node (ref "U8") (pin "39") (pinfunction "GND_39") (pintype "power_in"))
      (node (ref "U8") (pin "4") (pinfunction "GND_4") (pintype "power_in"))
      (node (ref "U8") (pin "5") (pinfunction "GND_5") (pintype "power_in"))
      (node (ref "U8") (pin "6") (pinfunction "GND_6") (pintype "power_in"))
      (node (ref "U8") (pin "7") (pinfunction "GND_7") (pintype "power_in"))
      (node (ref "U8") (pin "8") (pinfunction "GND_8") (pintype "power_in"))
      (node (ref "U8") (pin "9") (pinfunction "GND_9") (pintype "power_in"))
      (node (ref "U8") (pin "A3") (pinfunction "GND_A3") (pintype "power_in"))
      (node (ref "U8") (pin "C1") (pinfunction "GND_C1") (pintype "power_in"))
      (node (ref "U8") (pin "C3") (pinfunction "GND_C3") (pintype "power_in"))
      (node (ref "U8") (pin "C4") (pinfunction "GND_C4") (pintype "power_in"))
      (node (ref "U8") (pin "C7") (pinfunction "GND_C7") (pintype "power_in"))
      (node (ref "U8") (pin "D7") (pinfunction "GND_D7") (pintype "power_in"))
      (node (ref "U9") (pin "4") (pinfunction "GND_4") (pintype "bidirectional"))
    )
    (net (code "20") (name "LED_BLUE") (class "Default")
      (node (ref "R3") (pin "1") (pinfunction "P$1_1") (pintype "passive"))
      (node (ref "U8") (pin "A9") (pinfunction "LED_BLUE/PB_8_A9") (pintype "output"))
    )
    (net (code "21") (name "LED_GREEN") (class "Default")
      (node (ref "R1") (pin "1") (pinfunction "P$1_1") (pintype "passive"))
      (node (ref "U8") (pin "A8") (pinfunction "LED_GREEN/PB_6_A8") (pintype "bidirectional"))
    )
    (net (code "22") (name "LED_RED") (class "Default")
      (node (ref "R2") (pin "1") (pinfunction "P$1_1") (pintype "passive"))
      (node (ref "U8") (pin "A7") (pinfunction "LED_RED/PE_0_A7") (pintype "output"))
    )
    (net (code "23") (name "Net-(C1-P$1)") (class "Default")
      (node (ref "C1") (pin "1") (pinfunction "P$1_1") (pintype "passive"))
      (node (ref "C2") (pin "1") (pinfunction "P$1_1") (pintype "passive"))
      (node (ref "CON1") (pin "VBUS") (pinfunction "VBUS_VBUS") (pintype "bidirectional"))
      (node (ref "U2") (pin "1") (pinfunction "IN_1") (pintype "bidirectional"))
    )
    (net (code "24") (name "Net-(C10-P$1)") (class "Default")
      (node (ref "C10") (pin "1") (pinfunction "P$1_1") (pintype "passive"))
      (node (ref "R9") (pin "2") (pinfunction "P$2_2") (pintype "passive"))
      (node (ref "U1") (pin "2") (pinfunction "IF_NRESET_2") (pintype "bidirectional"))
    )
    (net (code "25") (name "Net-(C12-P$1)") (class "Default")
      (node (ref "C12") (pin "1") (pinfunction "P$1_1") (pintype "passive"))
      (node (ref "R7") (pin "2") (pinfunction "P$2_2") (pintype "passive"))
      (node (ref "U1") (pin "13") (pinfunction "USB_D-_13") (pintype "bidirectional"))
    )
    (net (code "26") (name "Net-(C13-P$1)") (class "Default")
      (node (ref "C13") (pin "1") (pinfunction "P$1_1") (pintype "passive"))
      (node (ref "R4") (pin "2") (pinfunction "P$2_2") (pintype "passive"))
      (node (ref "R8") (pin "2") (pinfunction "P$2_2") (pintype "passive"))
      (node (ref "U1") (pin "14") (pinfunction "USB_D+_14") (pintype "bidirectional"))
    )
    (net (code "27") (name "Net-(C14-P$1)") (class "Default")
      (node (ref "C14") (pin "1") (pinfunction "P$1_1") (pintype "passive"))
      (node (ref "U1") (pin "4") (pinfunction "XTALIN_4") (pintype "bidirectional"))
      (node (ref "Y1") (pin "P$1") (pinfunction "1_P$1") (pintype "passive"))
    )
    (net (code "28") (name "Net-(C15-P$1)") (class "Default")
      (node (ref "C15") (pin "1") (pinfunction "P$1_1") (pintype "passive"))
      (node (ref "U1") (pin "5") (pinfunction "XTALOUT_5") (pintype "bidirectional"))
      (node (ref "Y1") (pin "P$3") (pinfunction "2_P$3") (pintype "passive"))
    )
    (net (code "29") (name "Net-(C18-P$1)") (class "Default")
      (node (ref "C18") (pin "1") (pinfunction "P$1_1") (pintype "passive"))
      (node (ref "LCD1") (pin "P$9") (pinfunction "C1-_P$9") (pintype "bidirectional"))
    )
    (net (code "30") (name "Net-(C18-P$2)") (class "Default")
      (node (ref "C18") (pin "2") (pinfunction "P$2_2") (pintype "passive"))
      (node (ref "LCD1") (pin "P$8") (pinfunction "C1+_P$8") (pintype "bidirectional"))
    )
    (net (code "31") (name "Net-(C19-P$1)") (class "Default")
      (node (ref "C19") (pin "1") (pinfunction "P$1_1") (pintype "passive"))
      (node (ref "LCD1") (pin "P$7") (pinfunction "C2+_P$7") (pintype "bidirectional"))
    )
    (net (code "32") (name "Net-(C19-P$2)") (class "Default")
      (node (ref "C19") (pin "2") (pinfunction "P$2_2") (pintype "passive"))
      (node (ref "LCD1") (pin "P$6") (pinfunction "C2-_P$6") (pintype "bidirectional"))
    )
    (net (code "33") (name "Net-(C20-P$1)") (class "Default")
      (node (ref "C20") (pin "1") (pinfunction "P$1_1") (pintype "passive"))
      (node (ref "LCD1") (pin "P$1") (pinfunction "V0_P$1") (pintype "bidirectional"))
    )
    (net (code "34") (name "Net-(C21-P$1)") (class "Default")
      (node (ref "C21") (pin "1") (pinfunction "P$1_1") (pintype "passive"))
      (node (ref "LCD1") (pin "P$2") (pinfunction "V1_P$2") (pintype "bidirectional"))
    )
    (net (code "35") (name "Net-(C22-P$1)") (class "Default")
      (node (ref "C22") (pin "1") (pinfunction "P$1_1") (pintype "passive"))
      (node (ref "LCD1") (pin "P$3") (pinfunction "V2_P$3") (pintype "bidirectional"))
    )
    (net (code "36") (name "Net-(C23-P$1)") (class "Default")
      (node (ref "C23") (pin "1") (pinfunction "P$1_1") (pintype "passive"))
      (node (ref "LCD1") (pin "P$4") (pinfunction "V3_P$4") (pintype "bidirectional"))
    )
    (net (code "37") (name "Net-(C24-P$1)") (class "Default")
      (node (ref "C24") (pin "1") (pinfunction "P$1_1") (pintype "passive"))
      (node (ref "LCD1") (pin "P$5") (pinfunction "V4_P$5") (pintype "bidirectional"))
    )
    (net (code "38") (name "Net-(C25-P$1)") (class "Default")
      (node (ref "C25") (pin "1") (pinfunction "P$1_1") (pintype "passive"))
      (node (ref "LCD1") (pin "P$10") (pinfunction "VOUT_P$10") (pintype "bidirectional"))
    )
    (net (code "39") (name "Net-(R1-P$2)") (class "Default")
      (node (ref "LED0") (pin "4") (pinfunction "4_4") (pintype "passive"))
      (node (ref "R1") (pin "2") (pinfunction "P$2_2") (pintype "passive"))
    )
    (net (code "40") (name "Net-(R2-P$2)") (class "Default")
      (node (ref "LED0") (pin "1") (pinfunction "1_1") (pintype "passive"))
      (node (ref "R2") (pin "2") (pinfunction "P$2_2") (pintype "passive"))
    )
    (net (code "41") (name "Net-(R3-P$2)") (class "Default")
      (node (ref "LED0") (pin "3") (pinfunction "3_3") (pintype "passive"))
      (node (ref "R3") (pin "2") (pinfunction "P$2_2") (pintype "passive"))
    )
    (net (code "42") (name "Net-(R5-P$1)") (class "Default")
      (node (ref "LED7") (pin "A") (pinfunction "A_A") (pintype "passive"))
      (node (ref "R5") (pin "1") (pinfunction "P$1_1") (pintype "passive"))
    )
    (net (code "43") (name "Net-(R6-P$1)") (class "Default")
      (node (ref "LED6") (pin "A") (pinfunction "A_A") (pintype "passive"))
      (node (ref "R6") (pin "1") (pinfunction "P$1_1") (pintype "passive"))
    )
    (net (code "44") (name "Net-(R8-P$1)") (class "Default")
      (node (ref "R8") (pin "1") (pinfunction "P$1_1") (pintype "passive"))
      (node (ref "T1") (pin "3") (pinfunction "D_3") (pintype "passive"))
    )
    (net (code "45") (name "Net-(R10-P$2)") (class "Default")
      (node (ref "R10") (pin "2") (pinfunction "P$2_2") (pintype "passive"))
      (node (ref "U1") (pin "9") (pinfunction "USB_VBUS_9") (pintype "bidirectional"))
    )
    (net (code "46") (name "Net-(R11-P$1)") (class "Default")
      (node (ref "LED10") (pin "A") (pinfunction "A_A") (pintype "passive"))
      (node (ref "R11") (pin "1") (pinfunction "P$1_1") (pintype "passive"))
    )
    (net (code "47") (name "Net-(R11-P$2)") (class "Default")
      (node (ref "R11") (pin "2") (pinfunction "P$2_2") (pintype "passive"))
      (node (ref "U1") (pin "7") (pinfunction "LED_MSD_7") (pintype "bidirectional"))
    )
    (net (code "48") (name "Net-(R12-P$1)") (class "Default")
      (node (ref "LED8") (pin "C") (pinfunction "C_C") (pintype "passive"))
      (node (ref "R12") (pin "1") (pinfunction "P$1_1") (pintype "passive"))
    )
    (net (code "49") (name "Net-(R12-P$2)") (class "Default")
      (node (ref "R12") (pin "2") (pinfunction "P$2_2") (pintype "passive"))
      (node (ref "U1") (pin "12") (pinfunction "LED_HID_12") (pintype "bidirectional"))
    )
    (net (code "50") (name "Net-(R13-P$1)") (class "Default")
      (node (ref "LED9") (pin "C") (pinfunction "C_C") (pintype "passive"))
      (node (ref "R13") (pin "1") (pinfunction "P$1_1") (pintype "passive"))
    )
    (net (code "51") (name "Net-(R13-P$2)") (class "Default")
      (node (ref "R13") (pin "2") (pinfunction "P$2_2") (pintype "passive"))
      (node (ref "U1") (pin "21") (pinfunction "LED_UART_21") (pintype "bidirectional"))
    )
    (net (code "52") (name "Net-(R14-P$1)") (class "Default")
      (node (ref "LED5") (pin "A") (pinfunction "A_A") (pintype "passive"))
      (node (ref "R14") (pin "1") (pinfunction "P$1_1") (pintype "passive"))
    )
    (net (code "53") (name "Net-(R15-P$1)") (class "Default")
      (node (ref "LED2") (pin "A") (pinfunction "A_A") (pintype "passive"))
      (node (ref "R15") (pin "1") (pinfunction "P$1_1") (pintype "passive"))
    )
    (net (code "54") (name "Net-(R16-P$1)") (class "Default")
      (node (ref "LED4") (pin "A") (pinfunction "A_A") (pintype "passive"))
      (node (ref "R16") (pin "1") (pinfunction "P$1_1") (pintype "passive"))
    )
    (net (code "55") (name "Net-(R17-P$1)") (class "Default")
      (node (ref "LED3") (pin "A") (pinfunction "A_A") (pintype "passive"))
      (node (ref "R17") (pin "1") (pinfunction "P$1_1") (pintype "passive"))
    )
    (net (code "56") (name "Net-(R18-P$1)") (class "Default")
      (node (ref "LED1") (pin "A") (pinfunction "A_A") (pintype "passive"))
      (node (ref "R18") (pin "1") (pinfunction "P$1_1") (pintype "passive"))
    )
    (net (code "57") (name "Net-(R19-P$1)") (class "Default")
      (node (ref "R19") (pin "1") (pinfunction "P$1_1") (pintype "passive"))
      (node (ref "U3") (pin "5") (pinfunction "INT_5") (pintype "bidirectional"))
    )
    (net (code "58") (name "Net-(R21-P$2)") (class "Default")
      (node (ref "LCD1") (pin "A") (pinfunction "A_A") (pintype "bidirectional"))
      (node (ref "R21") (pin "2") (pinfunction "P$2_2") (pintype "passive"))
    )
    (net (code "59") (name "Net-(R24-P$2)") (class "Default")
      (node (ref "R24") (pin "2") (pinfunction "P$2_2") (pintype "passive"))
      (node (ref "U8") (pin "TP5") (pinfunction "TGT_NRESET_TP5") (pintype "input"))
    )
    (net (code "60") (name "Net-(R26-P$1)") (class "Default")
      (node (ref "R26") (pin "1") (pinfunction "P$1_1") (pintype "passive"))
      (node (ref "U3") (pin "2") (pinfunction "ADDR_SEL_2") (pintype "bidirectional"))
    )
    (net (code "61") (name "Net-(R27-P$2)") (class "Default")
      (node (ref "R27") (pin "2") (pinfunction "P$2_2") (pintype "passive"))
      (node (ref "U5") (pin "5") (pinfunction "XSHUT_5") (pintype "bidirectional"))
    )
    (net (code "62") (name "Net-(R28-P$1)") (class "Default")
      (node (ref "R28") (pin "1") (pinfunction "P$1_1") (pintype "passive"))
      (node (ref "U4") (pin "2") (pinfunction "ADDR_2") (pintype "bidirectional"))
    )
    (net (code "63") (name "Net-(R29-P$1)") (class "Default")
      (node (ref "R29") (pin "1") (pinfunction "P$1_1") (pintype "passive"))
      (node (ref "U7") (pin "1") (pinfunction "ADDR_1") (pintype "bidirectional"))
    )
    (net (code "64") (name "Net-(R30-P$1)") (class "Default")
      (node (ref "R30") (pin "1") (pinfunction "P$1_1") (pintype "passive"))
      (node (ref "U7") (pin "2") (pinfunction "~{RESET}_2") (pintype "bidirectional"))
    )
    (net (code "65") (name "Net-(R32-P$2)") (class "Default")
      (node (ref "R32") (pin "2") (pinfunction "P$2_2") (pintype "passive"))
      (node (ref "U7") (pin "7") (pinfunction "~{WAKE}_7") (pintype "bidirectional"))
    )
    (net (code "66") (name "Net-(RESET-S)") (class "Default")
      (node (ref "D6") (pin "K") (pinfunction "K_K") (pintype "passive"))
      (node (ref "RESET") (pin "P$2") (pinfunction "S_P$2") (pintype "passive"))
      (node (ref "U1") (pin "1") (pinfunction "NRESET_FB_BL_1") (pintype "bidirectional"))
      (node (ref "U1") (pin "3") (pinfunction "NRESET_FB_ISP_3") (pintype "bidirectional"))
    )
    (net (code "67") (name "Net-(T1-G)") (class "Default")
      (node (ref "T1") (pin "1") (pinfunction "G_1") (pintype "passive"))
      (node (ref "U1") (pin "15") (pinfunction "USB_SCON_15") (pintype "bidirectional"))
    )
    (net (code "68") (name "Net-(U7-PWM)") (class "Default")
      (node (ref "U7") (pin "4") (pinfunction "PWM_4") (pintype "bidirectional"))
      (node (ref "U7") (pin "5") (pinfunction "SENSE_5") (pintype "bidirectional"))
    )
    (net (code "69") (name "PA_3") (class "Default")
      (node (ref "LED6") (pin "C") (pinfunction "C_C") (pintype "passive"))
      (node (ref "U8") (pin "A18") (pinfunction "UART1_DSR/PA_3_A18") (pintype "input"))
    )
    (net (code "70") (name "PA_11") (class "Default")
      (node (ref "LED4") (pin "C") (pinfunction "C_C") (pintype "passive"))
      (node (ref "U8") (pin "A10") (pinfunction "UART1_CTS/PA_11_A10") (pintype "input"))
    )
    (net (code "71") (name "PA_12") (class "Default")
      (node (ref "LED2") (pin "C") (pinfunction "C_C") (pintype "passive"))
      (node (ref "U8") (pin "A12") (pinfunction "UART1_RTS/PA_12_A12") (pintype "output"))
    )
    (net (code "72") (name "PC_2") (class "Default")
      (node (ref "LED5") (pin "C") (pinfunction "C_C") (pintype "passive"))
      (node (ref "U8") (pin "A5") (pinfunction "UART1_DTR/PC_2_A5") (pintype "output"))
    )
    (net (code "73") (name "PD_8") (class "Default")
      (node (ref "LED3") (pin "C") (pinfunction "C_C") (pintype "passive"))
      (node (ref "U8") (pin "A15") (pinfunction "UART3_TX/PD_8_A15") (pintype "input"))
    )
    (net (code "74") (name "PD_9") (class "Default")
      (node (ref "LED1") (pin "C") (pinfunction "C_C") (pintype "passive"))
      (node (ref "U8") (pin "A14") (pinfunction "UART3_RX/PD_9_A14") (pintype "input"))
    )
    (net (code "75") (name "PD_11") (class "Default")
      (node (ref "U14") (pin "4") (pinfunction "A3_4") (pintype "bidirectional"))
      (node (ref "U8") (pin "A16") (pinfunction "UART3_CTS/PD_11_A16") (pintype "input"))
    )
    (net (code "76") (name "PD_12") (class "Default")
      (node (ref "U14") (pin "3") (pinfunction "A2_3") (pintype "bidirectional"))
      (node (ref "U8") (pin "A17") (pinfunction "UART3_RTS/PD_12_A17") (pintype "input"))
    )
    (net (code "77") (name "PE_9") (class "Default")
      (node (ref "U14") (pin "1") (pinfunction "A1_1") (pintype "bidirectional"))
      (node (ref "U8") (pin "C12") (pinfunction "PE_9_C12") (pintype "input"))
    )
    (net (code "78") (name "PE_11") (class "Default")
      (node (ref "U14") (pin "8") (pinfunction "A7_8") (pintype "bidirectional"))
      (node (ref "U8") (pin "C11") (pinfunction "SPI_SSEL/PE_11_C11") (pintype "input"))
    )
    (net (code "79") (name "PE_12") (class "Default")
      (node (ref "U14") (pin "5") (pinfunction "A4_5") (pintype "bidirectional"))
      (node (ref "U8") (pin "C8") (pinfunction "SPI_SCK/PE_12_C8") (pintype "input"))
    )
    (net (code "80") (name "PE_13") (class "Default")
      (node (ref "U14") (pin "7") (pinfunction "A6_7") (pintype "bidirectional"))
      (node (ref "U8") (pin "C6") (pinfunction "SPI_MISO/PE_13_C6") (pintype "input"))
    )
    (net (code "81") (name "PE_14") (class "Default")
      (node (ref "U14") (pin "6") (pinfunction "A5_6") (pintype "bidirectional"))
      (node (ref "U8") (pin "C10") (pinfunction "SPI_MOSI/PE_14_C10") (pintype "input"))
    )
    (net (code "82") (name "PF_0") (class "Default")
      (node (ref "U13") (pin "1") (pinfunction "A1_1") (pintype "bidirectional"))
      (node (ref "U8") (pin "C18") (pinfunction "I2C_SDA/PF_0_C18") (pintype "input"))
    )
    (net (code "83") (name "PF_1") (class "Default")
      (node (ref "U13") (pin "3") (pinfunction "A2_3") (pintype "bidirectional"))
      (node (ref "U8") (pin "C17") (pinfunction "I2C_SCL/PF_1_C17") (pintype "input"))
    )
    (net (code "84") (name "PF_2") (class "Default")
      (node (ref "U13") (pin "4") (pinfunction "A3_4") (pintype "bidirectional"))
      (node (ref "U8") (pin "A6") (pinfunction "SW0/PF_2_A6") (pintype "input"))
    )
    (net (code "85") (name "PF_6") (class "Default")
      (node (ref "LED7") (pin "C") (pinfunction "C_C") (pintype "passive"))
      (node (ref "U8") (pin "C13") (pinfunction "PF_6_C13") (pintype "input"))
    )
    (net (code "86") (name "PG_4") (class "Default")
      (node (ref "U14") (pin "9") (pinfunction "A8_9") (pintype "bidirectional"))
      (node (ref "U8") (pin "C5") (pinfunction "PG_4_C5") (pintype "input"))
    )
    (net (code "87") (name "TGT_NRESET") (class "Default")
      (node (ref "R24") (pin "1") (pinfunction "P$1_1") (pintype "passive"))
      (node (ref "U13") (pin "7") (pinfunction "A6_7") (pintype "bidirectional"))
      (node (ref "U8") (pin "A1") (pinfunction "TGT_NRESET_A1") (pintype "input"))
    )
    (net (code "88") (name "TGT_RX") (class "Default")
      (node (ref "U13") (pin "5") (pinfunction "A4_5") (pintype "bidirectional"))
      (node (ref "U8") (pin "A13") (pinfunction "UART1_RX/TGT_RX/PA_10_A13") (pintype "input"))
    )
    (net (code "89") (name "TGT_SWCLK") (class "Default")
      (node (ref "U13") (pin "8") (pinfunction "A7_8") (pintype "bidirectional"))
      (node (ref "U8") (pin "TP9") (pinfunction "TGT_SWCLK_TP9") (pintype "input"))
    )
    (net (code "90") (name "TGT_SWDIO") (class "Default")
      (node (ref "U13") (pin "9") (pinfunction "A8_9") (pintype "bidirectional"))
      (node (ref "U8") (pin "TP7") (pinfunction "TGT_SWDIO_TP7") (pintype "input"))
    )
    (net (code "91") (name "TGT_TX") (class "Default")
      (node (ref "U13") (pin "6") (pinfunction "A5_6") (pintype "bidirectional"))
      (node (ref "U8") (pin "A11") (pinfunction "UART1_TX/TGT_TX/PA_9_A11") (pintype "output"))
    )
    (net (code "92") (name "TGT_USB_D+") (class "Default")
      (node (ref "CON1") (pin "D+") (pinfunction "D+_D+") (pintype "bidirectional"))
      (node (ref "R4") (pin "1") (pinfunction "P$1_1") (pintype "passive"))
    )
    (net (code "93") (name "TGT_USB_D-") (class "Default")
      (node (ref "CON1") (pin "D-") (pinfunction "D-_D-") (pintype "bidirectional"))
      (node (ref "R7") (pin "1") (pinfunction "P$1_1") (pintype "passive"))
    )
    (net (code "94") (name "unconnected-(CON2-Pad6)") (class "Default")
      (node (ref "CON2") (pin "6") (pinfunction "6_6") (pintype "passive"))
    )
    (net (code "95") (name "unconnected-(U1-NC2-Pad10)") (class "Default")
      (node (ref "U1") (pin "10") (pinfunction "NC2_10") (pintype "bidirectional"))
    )
    (net (code "96") (name "unconnected-(U1-NC3-Pad11)") (class "Default")
      (node (ref "U1") (pin "11") (pinfunction "NC3_11") (pintype "bidirectional"))
    )
    (net (code "97") (name "unconnected-(U1-NC4-Pad19)") (class "Default")
      (node (ref "U1") (pin "19") (pinfunction "NC4_19") (pintype "bidirectional"))
    )
    (net (code "98") (name "unconnected-(U1-NC5-Pad20)") (class "Default")
      (node (ref "U1") (pin "20") (pinfunction "NC5_20") (pintype "bidirectional"))
    )
    (net (code "99") (name "unconnected-(U1-NC6-Pad22)") (class "Default")
      (node (ref "U1") (pin "22") (pinfunction "NC6_22") (pintype "bidirectional"))
    )
    (net (code "100") (name "unconnected-(U1-NC7-Pad23)") (class "Default")
      (node (ref "U1") (pin "23") (pinfunction "NC7_23") (pintype "bidirectional"))
    )
    (net (code "101") (name "unconnected-(U1-NC8-Pad24)") (class "Default")
      (node (ref "U1") (pin "24") (pinfunction "NC8_24") (pintype "bidirectional"))
    )
    (net (code "102") (name "unconnected-(U1-NC9-Pad25)") (class "Default")
      (node (ref "U1") (pin "25") (pinfunction "NC9_25") (pintype "bidirectional"))
    )
    (net (code "103") (name "unconnected-(U1-NC10-Pad28)") (class "Default")
      (node (ref "U1") (pin "28") (pinfunction "NC10_28") (pintype "bidirectional"))
    )
    (net (code "104") (name "unconnected-(U1-NC11-Pad30)") (class "Default")
      (node (ref "U1") (pin "30") (pinfunction "NC11_30") (pintype "bidirectional"))
    )
    (net (code "105") (name "unconnected-(U1-SLEEP_NREQ-Pad27)") (class "Default")
      (node (ref "U1") (pin "27") (pinfunction "SLEEP_NREQ_27") (pintype "bidirectional"))
    )
    (net (code "106") (name "unconnected-(U1-TGT_SWO-Pad18)") (class "Default")
      (node (ref "U1") (pin "18") (pinfunction "TGT_SWO_18") (pintype "bidirectional"))
    )
    (net (code "107") (name "unconnected-(U1-WAKE_NREQ-Pad26)") (class "Default")
      (node (ref "U1") (pin "26") (pinfunction "WAKE_NREQ_26") (pintype "bidirectional"))
    )
    (net (code "108") (name "unconnected-(U4-ALERT-Pad3)") (class "Default")
      (node (ref "U4") (pin "3") (pinfunction "ALERT_3") (pintype "bidirectional"))
    )
    (net (code "109") (name "unconnected-(U4-~{RESET}-Pad6)") (class "Default")
      (node (ref "U4") (pin "6") (pinfunction "~{RESET}_6") (pintype "bidirectional"))
    )
    (net (code "110") (name "unconnected-(U5-DNC-Pad8)") (class "Default")
      (node (ref "U5") (pin "8") (pinfunction "DNC_8") (pintype "bidirectional"))
    )
    (net (code "111") (name "unconnected-(U5-GPIO1-Pad7)") (class "Default")
      (node (ref "U5") (pin "7") (pinfunction "GPIO1_7") (pintype "bidirectional"))
    )
    (net (code "112") (name "unconnected-(U6-INT_N-PadP$5)") (class "Default")
      (node (ref "U6") (pin "P$5") (pinfunction "INT_N_P$5") (pintype "bidirectional"))
    )
    (net (code "113") (name "unconnected-(U6-NC2-PadP$2)") (class "Default")
      (node (ref "U6") (pin "P$2") (pinfunction "NC2_P$2") (pintype "bidirectional"))
    )
    (net (code "114") (name "unconnected-(U6-NC10-PadP$10)") (class "Default")
      (node (ref "U6") (pin "P$10") (pinfunction "NC10_P$10") (pintype "bidirectional"))
    )
    (net (code "115") (name "unconnected-(U6-RSVD-PadP$1)") (class "Default")
      (node (ref "U6") (pin "P$1") (pinfunction "RSVD_P$1") (pintype "bidirectional"))
    )
    (net (code "116") (name "unconnected-(U7-AUX-Pad8)") (class "Default")
      (node (ref "U7") (pin "8") (pinfunction "AUX_8") (pintype "bidirectional"))
    )
    (net (code "117") (name "unconnected-(U7-~{INT}-Pad3)") (class "Default")
      (node (ref "U7") (pin "3") (pinfunction "~{INT}_3") (pintype "bidirectional"))
    )
    (net (code "118") (name "unconnected-(U8A-LPO_CLK-PadC16)") (class "Default")
      (node (ref "U8") (pin "C16") (pinfunction "LPO_CLK_C16") (pintype "input"))
    )
    (net (code "119") (name "unconnected-(U8A-RMII_CRSDV-PadD4)") (class "Default")
      (node (ref "U8") (pin "D4") (pinfunction "RMII_CRSDV_D4") (pintype "input"))
    )
    (net (code "120") (name "unconnected-(U8A-RMII_MDC-PadC14)") (class "Default")
      (node (ref "U8") (pin "C14") (pinfunction "RMII_MDC_C14") (pintype "output"))
    )
    (net (code "121") (name "unconnected-(U8A-RMII_MDIO-PadC15)") (class "Default")
      (node (ref "U8") (pin "C15") (pinfunction "RMII_MDIO_C15") (pintype "bidirectional"))
    )
    (net (code "122") (name "unconnected-(U8A-RMII_REFCLK-PadD8)") (class "Default")
      (node (ref "U8") (pin "D8") (pinfunction "RMII_REFCLK_D8") (pintype "input"))
    )
    (net (code "123") (name "unconnected-(U8A-RMII_RXD0-PadD5)") (class "Default")
      (node (ref "U8") (pin "D5") (pinfunction "RMII_RXD0_D5") (pintype "input"))
    )
    (net (code "124") (name "unconnected-(U8A-RMII_RXD1-PadD6)") (class "Default")
      (node (ref "U8") (pin "D6") (pinfunction "RMII_RXD1_D6") (pintype "input"))
    )
    (net (code "125") (name "unconnected-(U8A-RMII_TXD0-PadD1)") (class "Default")
      (node (ref "U8") (pin "D1") (pinfunction "RMII_TXD0_D1") (pintype "output"))
    )
    (net (code "126") (name "unconnected-(U8A-RMII_TXD1-PadD2)") (class "Default")
      (node (ref "U8") (pin "D2") (pinfunction "RMII_TXD1_D2") (pintype "output"))
    )
    (net (code "127") (name "unconnected-(U8A-RMII_TXEN-PadD3)") (class "Default")
      (node (ref "U8") (pin "D3") (pinfunction "RMII_TXEN_D3") (pintype "output"))
    )
    (net (code "128") (name "unconnected-(U8B-NC-PadB1)") (class "Default")
      (node (ref "U8") (pin "B1") (pinfunction "NC_B1") (pintype "no_connect"))
    )
    (net (code "129") (name "unconnected-(U8B-NC-PadB2)") (class "Default")
      (node (ref "U8") (pin "B2") (pinfunction "NC_B2") (pintype "no_connect"))
    )
    (net (code "130") (name "unconnected-(U8B-NC-PadB3)") (class "Default")
      (node (ref "U8") (pin "B3") (pinfunction "NC_B3") (pintype "no_connect"))
    )
    (net (code "131") (name "unconnected-(U8B-NC-PadB4)") (class "Default")
      (node (ref "U8") (pin "B4") (pinfunction "NC_B4") (pintype "no_connect"))
    )
    (net (code "132") (name "unconnected-(U8B-NC-PadB5)") (class "Default")
      (node (ref "U8") (pin "B5") (pinfunction "NC_B5") (pintype "no_connect"))
    )
    (net (code "133") (name "unconnected-(U8B-NC-PadB6)") (class "Default")
      (node (ref "U8") (pin "B6") (pinfunction "NC_B6") (pintype "no_connect"))
    )
    (net (code "134") (name "unconnected-(U8B-NC-PadB7)") (class "Default")
      (node (ref "U8") (pin "B7") (pinfunction "NC_B7") (pintype "no_connect"))
    )
    (net (code "135") (name "unconnected-(U8B-NC-PadB8)") (class "Default")
      (node (ref "U8") (pin "B8") (pinfunction "NC_B8") (pintype "no_connect"))
    )
    (net (code "136") (name "unconnected-(U8B-NC-PadC2)") (class "Default")
      (node (ref "U8") (pin "C2") (pinfunction "NC_C2") (pintype "no_connect"))
    )
    (net (code "137") (name "unconnected-(U8B-NC-PadC9)") (class "Default")
      (node (ref "U8") (pin "C9") (pinfunction "NC_C9") (pintype "no_connect"))
    )
    (net (code "138") (name "unconnected-(U8B-TEST_PAD1-PadTP1)") (class "Default")
      (node (ref "U8") (pin "TP1") (pinfunction "TEST_PAD1_TP1") (pintype "no_connect"))
    )
    (net (code "139") (name "unconnected-(U8B-TEST_PAD2-PadTP2)") (class "Default")
      (node (ref "U8") (pin "TP2") (pinfunction "TEST_PAD2_TP2") (pintype "no_connect"))
    )
    (net (code "140") (name "unconnected-(U8B-TEST_PAD3-PadTP3)") (class "Default")
      (node (ref "U8") (pin "TP3") (pinfunction "TEST_PAD3_TP3") (pintype "no_connect"))
    )
    (net (code "141") (name "unconnected-(U8B-TEST_PAD4-PadTP4)") (class "Default")
      (node (ref "U8") (pin "TP4") (pinfunction "TEST_PAD4_TP4") (pintype "no_connect"))
    )
    (net (code "142") (name "unconnected-(U8B-TEST_PAD6-PadTP6)") (class "Default")
      (node (ref "U8") (pin "TP6") (pinfunction "TEST_PAD6_TP6") (pintype "no_connect"))
    )
    (net (code "143") (name "unconnected-(U8B-TEST_PAD8-PadTP8)") (class "Default")
      (node (ref "U8") (pin "TP8") (pinfunction "TEST_PAD8_TP8") (pintype "no_connect"))
    )
    (net (code "144") (name "unconnected-(U8B-TEST_PAD10-PadTP10)") (class "Default")
      (node (ref "U8") (pin "TP10") (pinfunction "TEST_PAD10_TP10") (pintype "no_connect"))
    )
    (net (code "145") (name "unconnected-(U8B-TEST_PAD11-PadTP11)") (class "Default")
      (node (ref "U8") (pin "TP11") (pinfunction "TEST_PAD11_TP11") (pintype "no_connect"))
    )
    (net (code "146") (name "unconnected-(U8B-TEST_PAD12-PadTP12)") (class "Default")
      (node (ref "U8") (pin "TP12") (pinfunction "TEST_PAD12_TP12") (pintype "no_connect"))
    )
  )
)
